# napajalnik.net
KiCad netlist of a schematic drawn in EAGLE
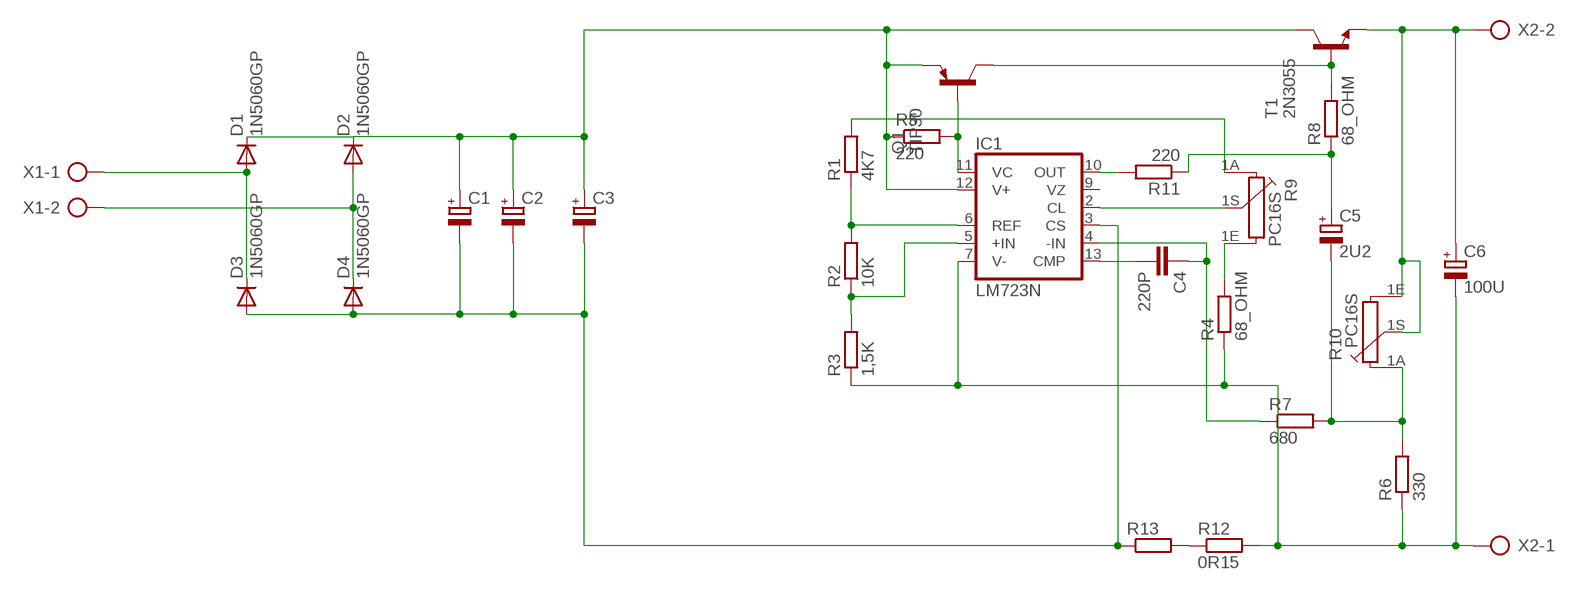
[diagram p0: schematic, sheet 1]

(export (version "E")
  (design (tool "Eeschema 10.0.6"))
  (components
    (comp (ref "C1")
      (value "CPOL-EUE10-20")
      (footprint "eagle-import:EB20D")
      (libsource (lib "eagle-import") (part "CPOL-EUE10-20"))
    )
    (comp (ref "C2")
      (value "CPOL-EUE10-20")
      (footprint "eagle-import:EB20D")
      (libsource (lib "eagle-import") (part "CPOL-EUE10-20"))
    )
    (comp (ref "C3")
      (value "CPOL-EUE10-20")
      (footprint "eagle-import:EB20D")
      (libsource (lib "eagle-import") (part "CPOL-EUE10-20"))
    )
    (comp (ref "C4")
      (value "220P")
      (footprint "eagle-import:C050-035X075")
      (libsource (lib "eagle-import") (part "C-EU050-035X075"))
    )
    (comp (ref "C5")
      (value "2U2")
      (footprint "eagle-import:TAP5-45")
      (libsource (lib "eagle-import") (part "CPOL-EUTAP5-45"))
    )
    (comp (ref "C6")
      (value "100U")
      (footprint "eagle-import:TAP5-80")
      (libsource (lib "eagle-import") (part "CPOL-EUTAP5-80"))
    )
    (comp (ref "D1")
      (value "1N5060GP")
      (footprint "eagle-import:DO15-12")
      (libsource (lib "eagle-import") (part "1N5060GP"))
    )
    (comp (ref "D2")
      (value "1N5060GP")
      (footprint "eagle-import:DO15-12")
      (libsource (lib "eagle-import") (part "1N5060GP"))
    )
    (comp (ref "D3")
      (value "1N5060GP")
      (footprint "eagle-import:DO15-12")
      (libsource (lib "eagle-import") (part "1N5060GP"))
    )
    (comp (ref "D4")
      (value "1N5060GP")
      (footprint "eagle-import:DO15-12")
      (libsource (lib "eagle-import") (part "1N5060GP"))
    )
    (comp (ref "IC1")
      (value "LM723N")
      (footprint "eagle-import:DIL14")
      (libsource (lib "eagle-import") (part "723NLM"))
    )
    (comp (ref "Q1")
      (value "TIP30")
      (footprint "eagle-import:TO220")
      (libsource (lib "eagle-import") (part "TIP30"))
    )
    (comp (ref "R1")
      (value "4K7")
      (footprint "eagle-import:0411_15")
      (libsource (lib "eagle-import") (part "R-EU_0411/15"))
    )
    (comp (ref "R2")
      (value "10K")
      (footprint "eagle-import:0411_15")
      (libsource (lib "eagle-import") (part "R-EU_0411/15"))
    )
    (comp (ref "R3")
      (value "1,5K")
      (footprint "eagle-import:0411_15")
      (libsource (lib "eagle-import") (part "R-EU_0411/15"))
    )
    (comp (ref "R4")
      (value "68_OHM")
      (footprint "eagle-import:0411_15")
      (libsource (lib "eagle-import") (part "R-EU_0411/15"))
    )
    (comp (ref "R5")
      (value "220")
      (footprint "eagle-import:0411_15")
      (libsource (lib "eagle-import") (part "R-EU_0411/15"))
    )
    (comp (ref "R6")
      (value "330")
      (footprint "eagle-import:0411_15")
      (libsource (lib "eagle-import") (part "R-EU_0411/15"))
    )
    (comp (ref "R7")
      (value "680")
      (footprint "eagle-import:0411_15")
      (libsource (lib "eagle-import") (part "R-EU_0411/15"))
    )
    (comp (ref "R8")
      (value "68_OHM")
      (footprint "eagle-import:0411_15")
      (libsource (lib "eagle-import") (part "R-EU_0411/15"))
    )
    (comp (ref "R9")
      (value "PC16S")
      (footprint "eagle-import:PC16S")
      (libsource (lib "eagle-import") (part "PC16S"))
    )
    (comp (ref "R10")
      (value "PC16S")
      (footprint "eagle-import:PC16S")
      (libsource (lib "eagle-import") (part "PC16S"))
    )
    (comp (ref "R11")
      (value "220")
      (footprint "eagle-import:0411_15")
      (libsource (lib "eagle-import") (part "R-EU_0411/15"))
    )
    (comp (ref "R12")
      (value "0R15")
      (footprint "eagle-import:0411_15")
      (libsource (lib "eagle-import") (part "R-EU_0411/15"))
    )
    (comp (ref "R13")
      (value "R-EU_0411/15")
      (footprint "eagle-import:0411_15")
      (libsource (lib "eagle-import") (part "R-EU_0411/15"))
    )
    (comp (ref "T1")
      (value "2N3055")
      (footprint "eagle-import:TO3")
      (libsource (lib "eagle-import") (part "2N3055"))
    )
    (comp (ref "X1")
      (value "AK300/2")
      (footprint "eagle-import:AK300_2")
      (libsource (lib "eagle-import") (part "AK300/2"))
    )
    (comp (ref "X2")
      (value "AK300/2")
      (footprint "eagle-import:AK300_2")
      (libsource (lib "eagle-import") (part "AK300/2"))
    )
  )
  (nets
    (net (code "1") (name "Net-(C5-Pad+)") (class "Default")
      (node (ref "C5") (pin "+") (pinfunction "+_+") (pintype "passive"))
      (node (ref "R11") (pin "1") (pinfunction "1_1") (pintype "passive"))
      (node (ref "R8") (pin "1") (pinfunction "1_1") (pintype "passive"))
    )
    (net (code "2") (name "Net-(C5-Pad-)") (class "Default")
      (node (ref "C5") (pin "-") (pinfunction "-_-") (pintype "passive"))
      (node (ref "R10") (pin "1A") (pinfunction "1A_1A") (pintype "passive"))
      (node (ref "R6") (pin "2") (pinfunction "2_2") (pintype "passive"))
      (node (ref "R7") (pin "2") (pinfunction "2_2") (pintype "passive"))
    )
    (net (code "3") (name "Net-(IC1-+IN)") (class "Default")
      (node (ref "IC1") (pin "5") (pinfunction "+IN_5") (pintype "input"))
      (node (ref "R2") (pin "1") (pinfunction "1_1") (pintype "passive"))
      (node (ref "R3") (pin "2") (pinfunction "2_2") (pintype "passive"))
    )
    (net (code "4") (name "Net-(IC1--IN)") (class "Default")
      (node (ref "C4") (pin "1") (pinfunction "1_1") (pintype "passive"))
      (node (ref "IC1") (pin "4") (pinfunction "-IN_4") (pintype "input"))
      (node (ref "R7") (pin "1") (pinfunction "1_1") (pintype "passive"))
    )
    (net (code "5") (name "Net-(IC1-CL)") (class "Default")
      (node (ref "IC1") (pin "2") (pinfunction "CL_2") (pintype "input"))
      (node (ref "R9") (pin "1S") (pinfunction "1S_1S") (pintype "passive"))
    )
    (net (code "6") (name "Net-(IC1-CMP)") (class "Default")
      (node (ref "C4") (pin "2") (pinfunction "2_2") (pintype "passive"))
      (node (ref "IC1") (pin "13") (pinfunction "CMP_13") (pintype "passive"))
    )
    (net (code "7") (name "Net-(IC1-CS)") (class "Default")
      (node (ref "C1") (pin "-") (pinfunction "-_-") (pintype "passive"))
      (node (ref "C2") (pin "-") (pinfunction "-_-") (pintype "passive"))
      (node (ref "C3") (pin "-") (pinfunction "-_-") (pintype "passive"))
      (node (ref "D3") (pin "A") (pinfunction "A_A") (pintype "passive"))
      (node (ref "D4") (pin "A") (pinfunction "A_A") (pintype "passive"))
      (node (ref "IC1") (pin "3") (pinfunction "CS_3") (pintype "input"))
      (node (ref "R13") (pin "1") (pinfunction "1_1") (pintype "passive"))
    )
    (net (code "8") (name "Net-(IC1-OUT)") (class "Default")
      (node (ref "IC1") (pin "10") (pinfunction "OUT_10") (pintype "output"))
      (node (ref "R11") (pin "2") (pinfunction "2_2") (pintype "passive"))
    )
    (net (code "9") (name "Net-(IC1-REF)") (class "Default")
      (node (ref "IC1") (pin "6") (pinfunction "REF_6") (pintype "output"))
      (node (ref "R1") (pin "1") (pinfunction "1_1") (pintype "passive"))
      (node (ref "R2") (pin "2") (pinfunction "2_2") (pintype "passive"))
    )
    (net (code "10") (name "Net-(IC1-V+)") (class "Default")
      (node (ref "C1") (pin "+") (pinfunction "+_+") (pintype "passive"))
      (node (ref "C2") (pin "+") (pinfunction "+_+") (pintype "passive"))
      (node (ref "C3") (pin "+") (pinfunction "+_+") (pintype "passive"))
      (node (ref "D1") (pin "C") (pinfunction "C_C") (pintype "passive"))
      (node (ref "D2") (pin "C") (pinfunction "C_C") (pintype "passive"))
      (node (ref "IC1") (pin "12") (pinfunction "V+_12") (pintype "input"))
      (node (ref "Q1") (pin "3") (pinfunction "E_3") (pintype "passive"))
      (node (ref "R5") (pin "1") (pinfunction "1_1") (pintype "passive"))
      (node (ref "T1") (pin "C") (pinfunction "C_C") (pintype "passive"))
      (node (ref "T1") (pin "C/") (pinfunction "C_C/") (pintype "passive"))
    )
    (net (code "11") (name "Net-(IC1-V-)") (class "Default")
      (node (ref "C6") (pin "-") (pinfunction "-_-") (pintype "passive"))
      (node (ref "IC1") (pin "7") (pinfunction "V-_7") (pintype "input"))
      (node (ref "R12") (pin "2") (pinfunction "2_2") (pintype "passive"))
      (node (ref "R3") (pin "1") (pinfunction "1_1") (pintype "passive"))
      (node (ref "R4") (pin "1") (pinfunction "1_1") (pintype "passive"))
      (node (ref "R6") (pin "1") (pinfunction "1_1") (pintype "passive"))
      (node (ref "X2") (pin "1") (pinfunction "KL_1") (pintype "passive"))
    )
    (net (code "12") (name "Net-(IC1-VC)") (class "Default")
      (node (ref "IC1") (pin "11") (pinfunction "VC_11") (pintype "input"))
      (node (ref "Q1") (pin "1") (pinfunction "B_1") (pintype "passive"))
      (node (ref "R5") (pin "2") (pinfunction "2_2") (pintype "passive"))
    )
    (net (code "13") (name "Net-(Q1-C)") (class "Default")
      (node (ref "Q1") (pin "2") (pinfunction "C_2") (pintype "passive"))
      (node (ref "R8") (pin "2") (pinfunction "2_2") (pintype "passive"))
      (node (ref "T1") (pin "B") (pinfunction "B_B") (pintype "passive"))
    )
    (net (code "14") (name "Net-(R1-Pad2)") (class "Default")
      (node (ref "R1") (pin "2") (pinfunction "2_2") (pintype "passive"))
      (node (ref "R9") (pin "1A") (pinfunction "1A_1A") (pintype "passive"))
    )
    (net (code "15") (name "Net-(R4-Pad2)") (class "Default")
      (node (ref "R4") (pin "2") (pinfunction "2_2") (pintype "passive"))
      (node (ref "R9") (pin "1E") (pinfunction "1E_1E") (pintype "passive"))
    )
    (net (code "16") (name "Net-(R12-Pad1)") (class "Default")
      (node (ref "R12") (pin "1") (pinfunction "1_1") (pintype "passive"))
      (node (ref "R13") (pin "2") (pinfunction "2_2") (pintype "passive"))
    )
    (net (code "17") (name "Net-(X1A-KL)") (class "Default")
      (node (ref "D1") (pin "A") (pinfunction "A_A") (pintype "passive"))
      (node (ref "D3") (pin "C") (pinfunction "C_C") (pintype "passive"))
      (node (ref "X1") (pin "1") (pinfunction "KL_1") (pintype "passive"))
    )
    (net (code "18") (name "Net-(X1B-KL)") (class "Default")
      (node (ref "D2") (pin "A") (pinfunction "A_A") (pintype "passive"))
      (node (ref "D4") (pin "C") (pinfunction "C_C") (pintype "passive"))
      (node (ref "X1") (pin "2") (pinfunction "KL_2") (pintype "passive"))
    )
    (net (code "19") (name "Net-(X2B-KL)") (class "Default")
      (node (ref "C6") (pin "+") (pinfunction "+_+") (pintype "passive"))
      (node (ref "R10") (pin "1E") (pinfunction "1E_1E") (pintype "passive"))
      (node (ref "R10") (pin "1S") (pinfunction "1S_1S") (pintype "passive"))
      (node (ref "T1") (pin "E") (pinfunction "E_E") (pintype "passive"))
      (node (ref "X2") (pin "2") (pinfunction "KL_2") (pintype "passive"))
    )
    (net (code "20") (name "unconnected-(IC1-VZ-Pad9)") (class "Default")
      (node (ref "IC1") (pin "9") (pinfunction "VZ_9") (pintype "output"))
    )
  )
)
